# USB.net
KiCad netlist of a schematic drawn in Altium Designer
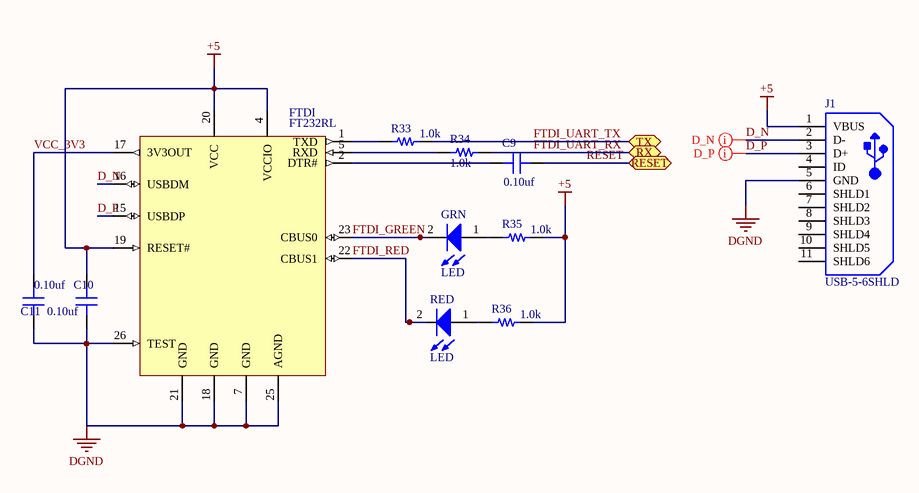
[diagram p0: USB.SchDoc]

(export (version "E")
  (design (tool "Eeschema 10.0.6"))
  (components
    (comp (ref "C9")
      (value "0.10uf")
      (footprint "CAP 0603/1608")
      (fields
        (field (name "Comment") "Capacitor MLCC 0.10uf 25V CAP 0603/1608")
        (field (name "CREATED_BY") "Nick Mah")
      )
      (libsource (lib "Altium-Lib") (part "Capacitor"))
    )
    (comp (ref "C10")
      (value "0.10uf")
      (footprint "CAP 0603/1608")
      (fields
        (field (name "Comment") "Capacitor MLCC 0.10uf 25V CAP 0603/1608")
        (field (name "CREATED_BY") "Nick Mah")
      )
      (libsource (lib "Altium-Lib") (part "Capacitor"))
    )
    (comp (ref "C11")
      (value "0.10uf")
      (footprint "CAP 0603/1608")
      (fields
        (field (name "Comment") "Capacitor MLCC 0.10uf 25V CAP 0603/1608")
        (field (name "CREATED_BY") "Nick Mah")
      )
      (libsource (lib "Altium-Lib") (part "Capacitor"))
    )
    (comp (ref "FTDI")
      (value "FT232RL")
      (footprint "SSOP-28")
      (fields (field (name "CREATED_BY") "Kyle"))
      (libsource (lib "Altium-Lib") (part "FT232RL"))
    )
    (comp (ref "GRN") (value "LED") (footprint "0805_LED") (libsource (lib "Altium-Lib") (part "LED")))
    (comp (ref "J1")
      (value "USB-5-6SHLD")
      (footprint "TECO-1981568-5_V")
      (description "USB Micro Type B")
      (fields (field (name "MFRPARTNO") "1981568-1") (field (name "CREATED_BY") "Aiku"))
      (libsource (lib "Altium-Lib") (part "USB-5-6SHLD"))
    )
    (comp (ref "R33")
      (value "1.0k")
      (footprint "RES 0805/2012")
      (fields
        (field (name "TOLERANCE") "1%")
        (field (name "POWER") "1/4W")
        (field (name "Comment") "Resistor 1.0k 0805 1/4W 1%")
        (field (name "CREATED_BY") "Nick Mah")
      )
      (libsource (lib "Altium-Lib") (part "Resistor"))
    )
    (comp (ref "R34")
      (value "1.0k")
      (footprint "RES 0805/2012")
      (fields
        (field (name "TOLERANCE") "1%")
        (field (name "POWER") "1/4W")
        (field (name "Comment") "Resistor 1.0k 0805 1/4W 1%")
        (field (name "CREATED_BY") "Nick Mah")
      )
      (libsource (lib "Altium-Lib") (part "Resistor"))
    )
    (comp (ref "R35")
      (value "1.0k")
      (footprint "RES 0805/2012")
      (fields
        (field (name "TOLERANCE") "1%")
        (field (name "POWER") "1/4W")
        (field (name "Comment") "Resistor 1.0k 0805 1/4W 1%")
        (field (name "CREATED_BY") "Nick Mah")
      )
      (libsource (lib "Altium-Lib") (part "Resistor"))
    )
    (comp (ref "R36")
      (value "1.0k")
      (footprint "RES 0805/2012")
      (fields
        (field (name "TOLERANCE") "1%")
        (field (name "POWER") "1/4W")
        (field (name "Comment") "Resistor 1.0k 0805 1/4W 1%")
        (field (name "CREATED_BY") "Nick Mah")
      )
      (libsource (lib "Altium-Lib") (part "Resistor"))
    )
    (comp (ref "RED") (value "LED") (footprint "0805_LED") (libsource (lib "Altium-Lib") (part "LED")))
  )
  (nets
    (net (code "1") (name "+5") (class "Default")
      (node (ref "C10") (pin "2") (pinfunction "2_2") (pintype "passive"))
      (node (ref "FTDI") (pin "19") (pinfunction "RESET#_19") (pintype "input"))
      (node (ref "FTDI") (pin "20") (pinfunction "VCC_20") (pintype "passive"))
      (node (ref "FTDI") (pin "4") (pinfunction "VCCIO_4") (pintype "passive"))
      (node (ref "J1") (pin "1") (pinfunction "VBUS_1") (pintype "passive"))
      (node (ref "R35") (pin "2") (pinfunction "2_2") (pintype "passive"))
      (node (ref "R36") (pin "2") (pinfunction "2_2") (pintype "passive"))
    )
    (net (code "2") (name "/D_N") (class "Default")
      (node (ref "FTDI") (pin "16") (pinfunction "USBDM_16") (pintype "bidirectional"))
      (node (ref "J1") (pin "2") (pinfunction "D-_2") (pintype "passive"))
    )
    (net (code "3") (name "/D_P") (class "Default")
      (node (ref "FTDI") (pin "15") (pinfunction "USBDP_15") (pintype "bidirectional"))
      (node (ref "J1") (pin "3") (pinfunction "D+_3") (pintype "passive"))
    )
    (net (code "4") (name "/FTDI_GREEN") (class "Default")
      (node (ref "FTDI") (pin "23") (pinfunction "CBUS0_23") (pintype "bidirectional"))
      (node (ref "GRN") (pin "2") (pinfunction "K_2") (pintype "passive"))
    )
    (net (code "5") (name "/FTDI_RED") (class "Default")
      (node (ref "FTDI") (pin "22") (pinfunction "CBUS1_22") (pintype "bidirectional"))
      (node (ref "RED") (pin "2") (pinfunction "K_2") (pintype "passive"))
    )
    (net (code "6") (name "/FTDI_UART_RX") (class "Default")
      (node (ref "R34") (pin "2") (pinfunction "2_2") (pintype "passive"))
    )
    (net (code "7") (name "/FTDI_UART_TX") (class "Default")
      (node (ref "R33") (pin "2") (pinfunction "2_2") (pintype "passive"))
    )
    (net (code "8") (name "/RESET") (class "Default")
      (node (ref "C9") (pin "2") (pinfunction "2_2") (pintype "passive"))
    )
    (net (code "9") (name "/VCC_3V3") (class "Default")
      (node (ref "C11") (pin "2") (pinfunction "2_2") (pintype "passive"))
      (node (ref "FTDI") (pin "17") (pinfunction "3V3OUT_17") (pintype "output"))
    )
    (net (code "10") (name "DGND") (class "Default")
      (node (ref "C10") (pin "1") (pinfunction "1_1") (pintype "passive"))
      (node (ref "C11") (pin "1") (pinfunction "1_1") (pintype "passive"))
      (node (ref "FTDI") (pin "18") (pinfunction "GND_18") (pintype "passive"))
      (node (ref "FTDI") (pin "21") (pinfunction "GND_21") (pintype "passive"))
      (node (ref "FTDI") (pin "25") (pinfunction "AGND_25") (pintype "passive"))
      (node (ref "FTDI") (pin "26") (pinfunction "TEST_26") (pintype "input"))
      (node (ref "FTDI") (pin "7") (pinfunction "GND_7") (pintype "passive"))
      (node (ref "J1") (pin "5") (pinfunction "GND_5") (pintype "passive"))
    )
    (net (code "11") (name "Net-(FTDI-DTR#)") (class "Default")
      (node (ref "C9") (pin "1") (pinfunction "1_1") (pintype "passive"))
      (node (ref "FTDI") (pin "2") (pinfunction "DTR#_2") (pintype "output"))
    )
    (net (code "12") (name "Net-(FTDI-RXD)") (class "Default")
      (node (ref "FTDI") (pin "5") (pinfunction "RXD_5") (pintype "input"))
      (node (ref "R34") (pin "1") (pinfunction "1_1") (pintype "passive"))
    )
    (net (code "13") (name "Net-(FTDI-TXD)") (class "Default")
      (node (ref "FTDI") (pin "1") (pinfunction "TXD_1") (pintype "output"))
      (node (ref "R33") (pin "1") (pinfunction "1_1") (pintype "passive"))
    )
    (net (code "14") (name "Net-(GRN-A)") (class "Default")
      (node (ref "GRN") (pin "1") (pinfunction "A_1") (pintype "passive"))
      (node (ref "R35") (pin "1") (pinfunction "1_1") (pintype "passive"))
    )
    (net (code "15") (name "Net-(RED-A)") (class "Default")
      (node (ref "R36") (pin "1") (pinfunction "1_1") (pintype "passive"))
      (node (ref "RED") (pin "1") (pinfunction "A_1") (pintype "passive"))
    )
    (net (code "16") (name "unconnected-(J1-ID-Pad4)") (class "Default")
      (node (ref "J1") (pin "4") (pinfunction "ID_4") (pintype "passive"))
    )
    (net (code "17") (name "unconnected-(J1-SHLD1-Pad6)") (class "Default")
      (node (ref "J1") (pin "6") (pinfunction "SHLD1_6") (pintype "passive"))
    )
    (net (code "18") (name "unconnected-(J1-SHLD2-Pad7)") (class "Default")
      (node (ref "J1") (pin "7") (pinfunction "SHLD2_7") (pintype "passive"))
    )
    (net (code "19") (name "unconnected-(J1-SHLD3-Pad8)") (class "Default")
      (node (ref "J1") (pin "8") (pinfunction "SHLD3_8") (pintype "passive"))
    )
    (net (code "20") (name "unconnected-(J1-SHLD4-Pad9)") (class "Default")
      (node (ref "J1") (pin "9") (pinfunction "SHLD4_9") (pintype "passive"))
    )
    (net (code "21") (name "unconnected-(J1-SHLD5-Pad10)") (class "Default")
      (node (ref "J1") (pin "10") (pinfunction "SHLD5_10") (pintype "passive"))
    )
    (net (code "22") (name "unconnected-(J1-SHLD6-Pad11)") (class "Default")
      (node (ref "J1") (pin "11") (pinfunction "SHLD6_11") (pintype "passive"))
    )
  )
)
